# sumorobot-wifi-pcb.net
KiCad netlist of a schematic drawn in EAGLE
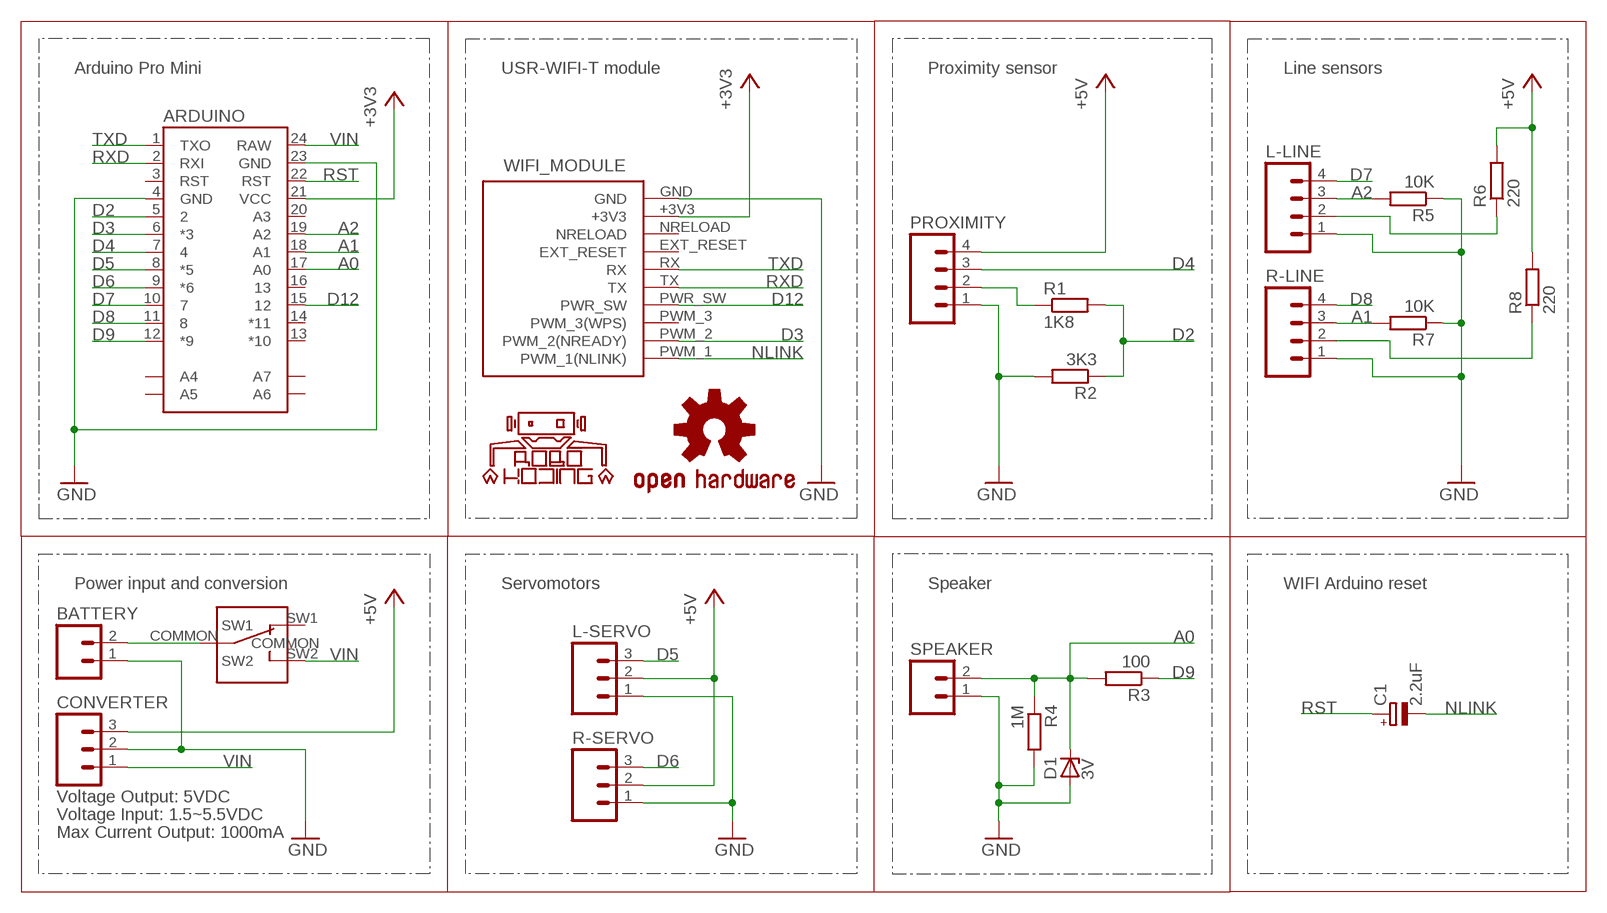
[diagram p0: schematic, sheet 1]

(export (version "E")
  (design (tool "Eeschema 10.0.6"))
  (components
    (comp (ref "ARDUINO")
      (value "ARDUINO_PRO_MINI")
      (footprint "eagle-import:ARDUINO_PRO_MINI")
      (libsource (lib "eagle-import") (part "ARDUINO_PRO_MINI"))
    )
    (comp (ref "BATTERY")
      (value "M02JST-PTH-VERT")
      (footprint "eagle-import:JST-2-PTH-VERT")
      (libsource (lib "eagle-import") (part "M02JST-PTH-VERT"))
    )
    (comp (ref "C1")
      (value "2.2uF")
      (footprint "eagle-import:E2-5")
      (libsource (lib "eagle-import") (part "CPOL-EUE2-5"))
    )
    (comp (ref "CONVERTER")
      (value "M03LOCK_LONGPADS")
      (footprint "eagle-import:1X03_LOCK_LONGPADS")
      (libsource (lib "eagle-import") (part "M03LOCK_LONGPADS"))
    )
    (comp (ref "D1")
      (value "3V")
      (footprint "eagle-import:DO35Z10")
      (libsource (lib "eagle-import") (part "1N821"))
    )
    (comp (ref "L-LINE")
      (value "M04LOCK_LONGPADS")
      (footprint "eagle-import:1X04_LOCK_LONGPADS")
      (libsource (lib "eagle-import") (part "M04LOCK_LONGPADS"))
    )
    (comp (ref "L-SERVO")
      (value "M03LOCK_LONGPADS")
      (footprint "eagle-import:1X03_LOCK_LONGPADS")
      (libsource (lib "eagle-import") (part "M03LOCK_LONGPADS"))
    )
    (comp (ref "LOGO1")
      (value "OSHW-LOGOM")
      (footprint "eagle-import:OSHW-LOGO-M")
      (libsource (lib "eagle-import") (part "OSHW-LOGOM"))
    )
    (comp (ref "LOGO2")
      (value "ROBOKODING-LOGOM")
      (footprint "eagle-import:ROBOKODING-LOGO-M")
      (libsource (lib "eagle-import") (part "ROBOKODING-LOGOM"))
    )
    (comp (ref "POWER")
      (value "SPDT_SLIDE_SWITCH")
      (footprint "eagle-import:SPDT_SLIDE_SWITCH")
      (libsource (lib "eagle-import") (part "SPDT_SLIDE_SWITCH"))
    )
    (comp (ref "PROXIMITY")
      (value "M04LOCK_LONGPADS")
      (footprint "eagle-import:1X04_LOCK_LONGPADS")
      (libsource (lib "eagle-import") (part "M04LOCK_LONGPADS"))
    )
    (comp (ref "R-LINE")
      (value "M04LOCK_LONGPADS")
      (footprint "eagle-import:1X04_LOCK_LONGPADS")
      (libsource (lib "eagle-import") (part "M04LOCK_LONGPADS"))
    )
    (comp (ref "R-SERVO")
      (value "M03LOCK_LONGPADS")
      (footprint "eagle-import:1X03_LOCK_LONGPADS")
      (libsource (lib "eagle-import") (part "M03LOCK_LONGPADS"))
    )
    (comp (ref "R1")
      (value "1K8")
      (footprint "eagle-import:0204_5")
      (libsource (lib "eagle-import") (part "R-EU_0204/5"))
    )
    (comp (ref "R2")
      (value "3K3")
      (footprint "eagle-import:0204_5")
      (libsource (lib "eagle-import") (part "R-EU_0204/5"))
    )
    (comp (ref "R3")
      (value "100")
      (footprint "eagle-import:0204_5")
      (libsource (lib "eagle-import") (part "R-EU_0204/5"))
    )
    (comp (ref "R4")
      (value "1M")
      (footprint "eagle-import:0204_5")
      (libsource (lib "eagle-import") (part "R-EU_0204/5"))
    )
    (comp (ref "R5")
      (value "10K")
      (footprint "eagle-import:0204_5")
      (libsource (lib "eagle-import") (part "R-EU_0204/5"))
    )
    (comp (ref "R6")
      (value "220")
      (footprint "eagle-import:0204_5")
      (libsource (lib "eagle-import") (part "R-EU_0204/5"))
    )
    (comp (ref "R7")
      (value "10K")
      (footprint "eagle-import:0204_5")
      (libsource (lib "eagle-import") (part "R-EU_0204/5"))
    )
    (comp (ref "R8")
      (value "220")
      (footprint "eagle-import:0204_5")
      (libsource (lib "eagle-import") (part "R-EU_0204/5"))
    )
    (comp (ref "SPEAKER")
      (value "M02LOCK_LONGPADS")
      (footprint "eagle-import:1X02_LOCK_LONGPADS")
      (libsource (lib "eagle-import") (part "M02LOCK_LONGPADS"))
    )
    (comp (ref "WIFI_MODULE")
      (value "USR_WIFI-T")
      (footprint "eagle-import:WIFI_MODULE-T")
      (libsource (lib "eagle-import") (part "USR_WIFI-T"))
    )
  )
  (nets
    (net (code "1") (name "+3V3") (class "Default")
      (node (ref "ARDUINO") (pin "21") (pinfunction "VCC_21") (pintype "bidirectional"))
      (node (ref "WIFI_MODULE") (pin "+3V3") (pinfunction "+3V3_+3V3") (pintype "power_in"))
    )
    (net (code "2") (name "+5V") (class "Default")
      (node (ref "CONVERTER") (pin "3") (pinfunction "3_3") (pintype "passive"))
      (node (ref "L-SERVO") (pin "2") (pinfunction "2_2") (pintype "passive"))
      (node (ref "PROXIMITY") (pin "4") (pinfunction "4_4") (pintype "passive"))
      (node (ref "R-SERVO") (pin "2") (pinfunction "2_2") (pintype "passive"))
      (node (ref "R6") (pin "2") (pinfunction "2_2") (pintype "passive"))
      (node (ref "R8") (pin "2") (pinfunction "2_2") (pintype "passive"))
    )
    (net (code "3") (name "/A0") (class "Default")
      (node (ref "ARDUINO") (pin "17") (pinfunction "A0_17") (pintype "bidirectional"))
      (node (ref "D1") (pin "C") (pinfunction "C_C") (pintype "passive"))
      (node (ref "R3") (pin "2") (pinfunction "2_2") (pintype "passive"))
      (node (ref "R4") (pin "1") (pinfunction "1_1") (pintype "passive"))
      (node (ref "SPEAKER") (pin "2") (pinfunction "2_2") (pintype "passive"))
    )
    (net (code "4") (name "/A1") (class "Default")
      (node (ref "ARDUINO") (pin "18") (pinfunction "A1_18") (pintype "bidirectional"))
      (node (ref "R-LINE") (pin "3") (pinfunction "3_3") (pintype "passive"))
      (node (ref "R7") (pin "2") (pinfunction "2_2") (pintype "passive"))
    )
    (net (code "5") (name "/A2") (class "Default")
      (node (ref "ARDUINO") (pin "19") (pinfunction "A2_19") (pintype "bidirectional"))
      (node (ref "L-LINE") (pin "3") (pinfunction "3_3") (pintype "passive"))
      (node (ref "R5") (pin "2") (pinfunction "2_2") (pintype "passive"))
    )
    (net (code "6") (name "/D2") (class "Default")
      (node (ref "ARDUINO") (pin "5") (pinfunction "2_5") (pintype "bidirectional"))
      (node (ref "R1") (pin "2") (pinfunction "2_2") (pintype "passive"))
      (node (ref "R2") (pin "1") (pinfunction "1_1") (pintype "passive"))
    )
    (net (code "7") (name "/D3") (class "Default")
      (node (ref "ARDUINO") (pin "6") (pinfunction "*3_6") (pintype "bidirectional"))
      (node (ref "WIFI_MODULE") (pin "PWM_2") (pinfunction "PWM_2(NREADY)_PWM_2") (pintype "bidirectional"))
    )
    (net (code "8") (name "/D4") (class "Default")
      (node (ref "ARDUINO") (pin "7") (pinfunction "4_7") (pintype "bidirectional"))
      (node (ref "PROXIMITY") (pin "3") (pinfunction "3_3") (pintype "passive"))
    )
    (net (code "9") (name "/D5") (class "Default")
      (node (ref "ARDUINO") (pin "8") (pinfunction "*5_8") (pintype "bidirectional"))
      (node (ref "L-SERVO") (pin "3") (pinfunction "3_3") (pintype "passive"))
    )
    (net (code "10") (name "/D6") (class "Default")
      (node (ref "ARDUINO") (pin "9") (pinfunction "*6_9") (pintype "bidirectional"))
      (node (ref "R-SERVO") (pin "3") (pinfunction "3_3") (pintype "passive"))
    )
    (net (code "11") (name "/D7") (class "Default")
      (node (ref "ARDUINO") (pin "10") (pinfunction "7_10") (pintype "bidirectional"))
      (node (ref "L-LINE") (pin "4") (pinfunction "4_4") (pintype "passive"))
    )
    (net (code "12") (name "/D8") (class "Default")
      (node (ref "ARDUINO") (pin "11") (pinfunction "8_11") (pintype "bidirectional"))
      (node (ref "R-LINE") (pin "4") (pinfunction "4_4") (pintype "passive"))
    )
    (net (code "13") (name "/D9") (class "Default")
      (node (ref "ARDUINO") (pin "12") (pinfunction "*9_12") (pintype "bidirectional"))
      (node (ref "R3") (pin "1") (pinfunction "1_1") (pintype "passive"))
    )
    (net (code "14") (name "/D12") (class "Default")
      (node (ref "ARDUINO") (pin "15") (pinfunction "12_15") (pintype "bidirectional"))
      (node (ref "WIFI_MODULE") (pin "PWR_SW") (pinfunction "PWR_SW_PWR_SW") (pintype "bidirectional"))
    )
    (net (code "15") (name "/NLINK") (class "Default")
      (node (ref "C1") (pin "-") (pinfunction "-_-") (pintype "passive"))
      (node (ref "WIFI_MODULE") (pin "PWM_1") (pinfunction "PWM_1(NLINK)_PWM_1") (pintype "bidirectional"))
    )
    (net (code "16") (name "/RST") (class "Default")
      (node (ref "ARDUINO") (pin "22") (pinfunction "RST_22") (pintype "bidirectional"))
      (node (ref "C1") (pin "+") (pinfunction "+_+") (pintype "passive"))
    )
    (net (code "17") (name "/RXD") (class "Default")
      (node (ref "ARDUINO") (pin "2") (pinfunction "RXI_2") (pintype "bidirectional"))
      (node (ref "WIFI_MODULE") (pin "TX") (pinfunction "TX_TX") (pintype "bidirectional"))
    )
    (net (code "18") (name "/TXD") (class "Default")
      (node (ref "ARDUINO") (pin "1") (pinfunction "TXO_1") (pintype "bidirectional"))
      (node (ref "WIFI_MODULE") (pin "RX") (pinfunction "RX_RX") (pintype "bidirectional"))
    )
    (net (code "19") (name "/VIN") (class "Default")
      (node (ref "ARDUINO") (pin "24") (pinfunction "RAW_24") (pintype "bidirectional"))
      (node (ref "CONVERTER") (pin "1") (pinfunction "1_1") (pintype "passive"))
      (node (ref "POWER") (pin "SW2") (pinfunction "SW2_SW2") (pintype "bidirectional"))
    )
    (net (code "20") (name "GND") (class "Default")
      (node (ref "ARDUINO") (pin "23") (pinfunction "GND_23") (pintype "bidirectional"))
      (node (ref "ARDUINO") (pin "4") (pinfunction "GND_4") (pintype "bidirectional"))
      (node (ref "BATTERY") (pin "1") (pinfunction "1_1") (pintype "passive"))
      (node (ref "CONVERTER") (pin "2") (pinfunction "2_2") (pintype "passive"))
      (node (ref "D1") (pin "A") (pinfunction "A_A") (pintype "passive"))
      (node (ref "L-LINE") (pin "1") (pinfunction "1_1") (pintype "passive"))
      (node (ref "L-SERVO") (pin "1") (pinfunction "1_1") (pintype "passive"))
      (node (ref "PROXIMITY") (pin "1") (pinfunction "1_1") (pintype "passive"))
      (node (ref "R-LINE") (pin "1") (pinfunction "1_1") (pintype "passive"))
      (node (ref "R-SERVO") (pin "1") (pinfunction "1_1") (pintype "passive"))
      (node (ref "R2") (pin "2") (pinfunction "2_2") (pintype "passive"))
      (node (ref "R4") (pin "2") (pinfunction "2_2") (pintype "passive"))
      (node (ref "R5") (pin "1") (pinfunction "1_1") (pintype "passive"))
      (node (ref "R7") (pin "1") (pinfunction "1_1") (pintype "passive"))
      (node (ref "SPEAKER") (pin "1") (pinfunction "1_1") (pintype "passive"))
      (node (ref "WIFI_MODULE") (pin "GND") (pinfunction "GND_GND") (pintype "power_in"))
    )
    (net (code "21") (name "Net-(BATTERY-Pad2)") (class "Default")
      (node (ref "BATTERY") (pin "2") (pinfunction "2_2") (pintype "passive"))
      (node (ref "POWER") (pin "COMMON") (pinfunction "COMMON_COMMON") (pintype "bidirectional"))
    )
    (net (code "22") (name "Net-(L-LINE-Pad2)") (class "Default")
      (node (ref "L-LINE") (pin "2") (pinfunction "2_2") (pintype "passive"))
      (node (ref "R6") (pin "1") (pinfunction "1_1") (pintype "passive"))
    )
    (net (code "23") (name "Net-(PROXIMITY-Pad2)") (class "Default")
      (node (ref "PROXIMITY") (pin "2") (pinfunction "2_2") (pintype "passive"))
      (node (ref "R1") (pin "1") (pinfunction "1_1") (pintype "passive"))
    )
    (net (code "24") (name "Net-(R-LINE-Pad2)") (class "Default")
      (node (ref "R-LINE") (pin "2") (pinfunction "2_2") (pintype "passive"))
      (node (ref "R8") (pin "1") (pinfunction "1_1") (pintype "passive"))
    )
    (net (code "25") (name "unconnected-(ARDUINO-*10-Pad13)") (class "Default")
      (node (ref "ARDUINO") (pin "13") (pinfunction "*10_13") (pintype "bidirectional"))
    )
    (net (code "26") (name "unconnected-(ARDUINO-*11-Pad14)") (class "Default")
      (node (ref "ARDUINO") (pin "14") (pinfunction "*11_14") (pintype "bidirectional"))
    )
    (net (code "27") (name "unconnected-(ARDUINO-13-Pad16)") (class "Default")
      (node (ref "ARDUINO") (pin "16") (pinfunction "13_16") (pintype "bidirectional"))
    )
    (net (code "28") (name "unconnected-(ARDUINO-A3-Pad20)") (class "Default")
      (node (ref "ARDUINO") (pin "20") (pinfunction "A3_20") (pintype "bidirectional"))
    )
    (net (code "29") (name "unconnected-(ARDUINO-RST-Pad3)") (class "Default")
      (node (ref "ARDUINO") (pin "3") (pinfunction "RST_3") (pintype "bidirectional"))
    )
    (net (code "30") (name "unconnected-(POWER-PadSW1)") (class "Default")
      (node (ref "POWER") (pin "SW1") (pinfunction "SW1_SW1") (pintype "bidirectional"))
    )
    (net (code "31") (name "unconnected-(WIFI_MODULE-PWM_3(WPS)-PadPWM_3)") (class "Default")
      (node (ref "WIFI_MODULE") (pin "PWM_3") (pinfunction "PWM_3(WPS)_PWM_3") (pintype "bidirectional"))
    )
    (net (code "32") (name "unconnected-(WIFI_MODULE-PadEXT_RESET)") (class "Default")
      (node (ref "WIFI_MODULE") (pin "EXT_RESET") (pinfunction "EXT_RESET_EXT_RESET") (pintype "bidirectional"))
    )
    (net (code "33") (name "unconnected-(WIFI_MODULE-PadNRELOAD)") (class "Default")
      (node (ref "WIFI_MODULE") (pin "NRELOAD") (pinfunction "NRELOAD_NRELOAD") (pintype "bidirectional"))
    )
  )
)
